# Mayfly_v0p5_outline.net
KiCad netlist of a schematic drawn in EAGLE
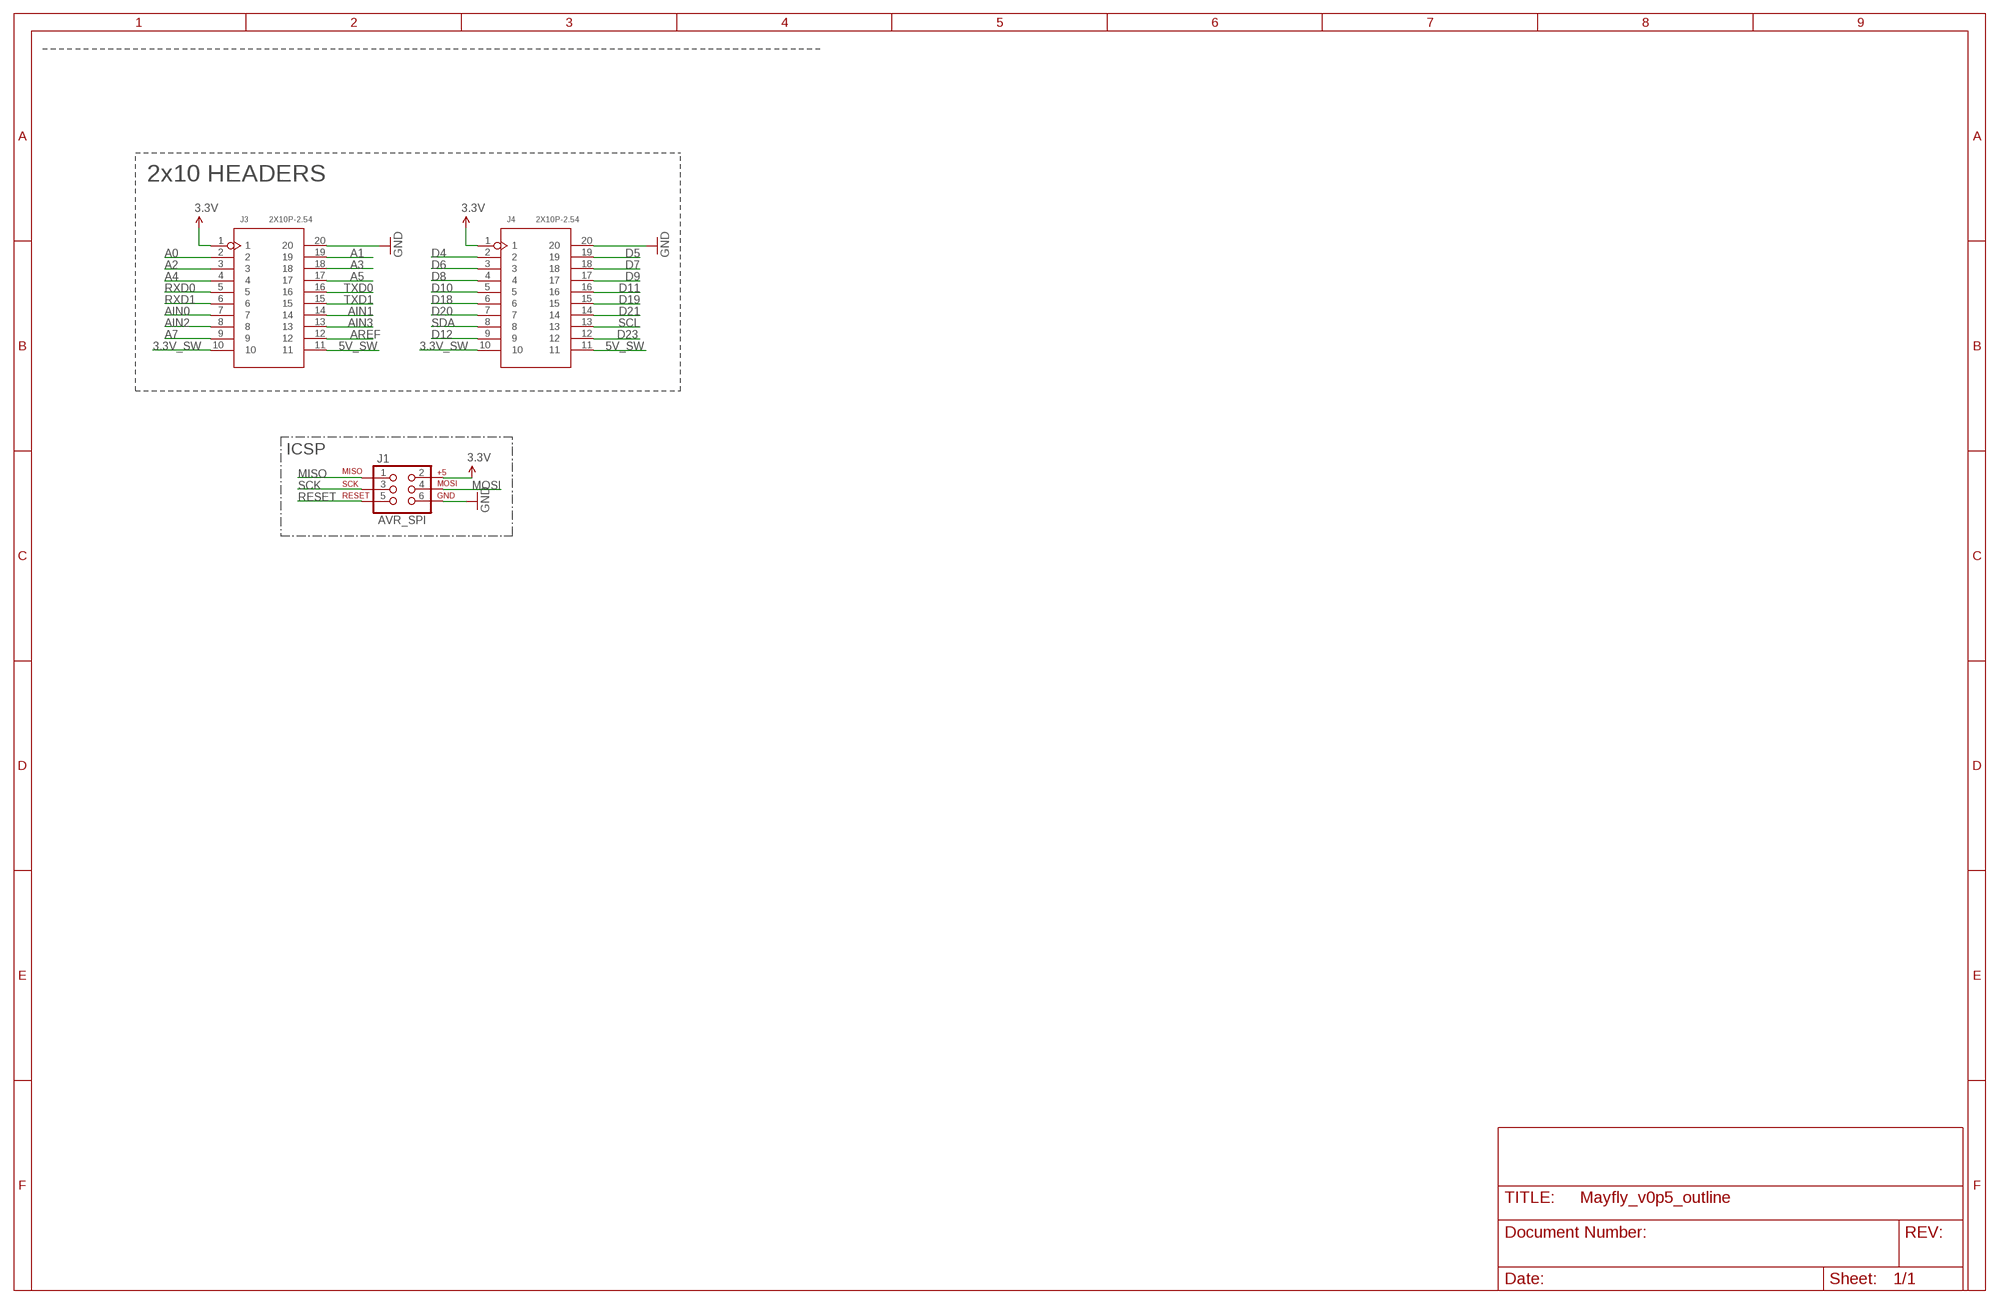
[diagram p0: schematic, sheet 1]

(export (version "E")
  (design (tool "Eeschema 10.0.6"))
  (components
    (comp (ref "J1")
      (value "AVR_SPI")
      (footprint "eagle-import:2X3-NS")
      (libsource (lib "eagle-import") (part "AVR_SPI_PRG_6NS"))
    )
    (comp (ref "J3")
      (value "2X10P-2.54")
      (footprint "eagle-import:H2X10-2.54")
      (fields (field (name "MPN") "F185-1210A0BA1"))
      (libsource (lib "eagle-import") (part "DIP-BLACK-FEMALE-HEADER(2X10P-2.54)-2.54"))
    )
    (comp (ref "J4")
      (value "2X10P-2.54")
      (footprint "eagle-import:H2X10-2.54")
      (fields (field (name "MPN") "F185-1210A0BA1"))
      (libsource (lib "eagle-import") (part "DIP-BLACK-FEMALE-HEADER(2X10P-2.54)-2.54"))
    )
  )
  (nets
    (net (code "1") (name "/3.3V_SW") (class "Default")
      (node (ref "J3") (pin "10") (pinfunction "10_10") (pintype "bidirectional"))
      (node (ref "J4") (pin "10") (pinfunction "10_10") (pintype "bidirectional"))
    )
    (net (code "2") (name "/5V_SW") (class "Default")
      (node (ref "J3") (pin "11") (pinfunction "11_11") (pintype "bidirectional"))
      (node (ref "J4") (pin "11") (pinfunction "11_11") (pintype "bidirectional"))
    )
    (net (code "3") (name "/A0") (class "Default")
      (node (ref "J3") (pin "2") (pinfunction "2_2") (pintype "bidirectional"))
    )
    (net (code "4") (name "/A1") (class "Default")
      (node (ref "J3") (pin "19") (pinfunction "19_19") (pintype "bidirectional"))
    )
    (net (code "5") (name "/A2") (class "Default")
      (node (ref "J3") (pin "3") (pinfunction "3_3") (pintype "bidirectional"))
    )
    (net (code "6") (name "/A3") (class "Default")
      (node (ref "J3") (pin "18") (pinfunction "18_18") (pintype "bidirectional"))
    )
    (net (code "7") (name "/A4") (class "Default")
      (node (ref "J3") (pin "4") (pinfunction "4_4") (pintype "bidirectional"))
    )
    (net (code "8") (name "/A5") (class "Default")
      (node (ref "J3") (pin "17") (pinfunction "17_17") (pintype "bidirectional"))
    )
    (net (code "9") (name "/A7") (class "Default")
      (node (ref "J3") (pin "9") (pinfunction "9_9") (pintype "bidirectional"))
    )
    (net (code "10") (name "/AIN0") (class "Default")
      (node (ref "J3") (pin "7") (pinfunction "7_7") (pintype "bidirectional"))
    )
    (net (code "11") (name "/AIN1") (class "Default")
      (node (ref "J3") (pin "14") (pinfunction "14_14") (pintype "bidirectional"))
    )
    (net (code "12") (name "/AIN2") (class "Default")
      (node (ref "J3") (pin "8") (pinfunction "8_8") (pintype "bidirectional"))
    )
    (net (code "13") (name "/AIN3") (class "Default")
      (node (ref "J3") (pin "13") (pinfunction "13_13") (pintype "bidirectional"))
    )
    (net (code "14") (name "/AREF") (class "Default")
      (node (ref "J3") (pin "12") (pinfunction "12_12") (pintype "bidirectional"))
    )
    (net (code "15") (name "/D4") (class "Default")
      (node (ref "J4") (pin "2") (pinfunction "2_2") (pintype "bidirectional"))
    )
    (net (code "16") (name "/D5") (class "Default")
      (node (ref "J4") (pin "19") (pinfunction "19_19") (pintype "bidirectional"))
    )
    (net (code "17") (name "/D6") (class "Default")
      (node (ref "J4") (pin "3") (pinfunction "3_3") (pintype "bidirectional"))
    )
    (net (code "18") (name "/D7") (class "Default")
      (node (ref "J4") (pin "18") (pinfunction "18_18") (pintype "bidirectional"))
    )
    (net (code "19") (name "/D8") (class "Default")
      (node (ref "J4") (pin "4") (pinfunction "4_4") (pintype "bidirectional"))
    )
    (net (code "20") (name "/D9") (class "Default")
      (node (ref "J4") (pin "17") (pinfunction "17_17") (pintype "bidirectional"))
    )
    (net (code "21") (name "/D10") (class "Default")
      (node (ref "J4") (pin "5") (pinfunction "5_5") (pintype "bidirectional"))
    )
    (net (code "22") (name "/D11") (class "Default")
      (node (ref "J4") (pin "16") (pinfunction "16_16") (pintype "bidirectional"))
    )
    (net (code "23") (name "/D12") (class "Default")
      (node (ref "J4") (pin "9") (pinfunction "9_9") (pintype "bidirectional"))
    )
    (net (code "24") (name "/D18") (class "Default")
      (node (ref "J4") (pin "6") (pinfunction "6_6") (pintype "bidirectional"))
    )
    (net (code "25") (name "/D19") (class "Default")
      (node (ref "J4") (pin "15") (pinfunction "15_15") (pintype "bidirectional"))
    )
    (net (code "26") (name "/D20") (class "Default")
      (node (ref "J4") (pin "7") (pinfunction "7_7") (pintype "bidirectional"))
    )
    (net (code "27") (name "/D21") (class "Default")
      (node (ref "J4") (pin "14") (pinfunction "14_14") (pintype "bidirectional"))
    )
    (net (code "28") (name "/D23") (class "Default")
      (node (ref "J4") (pin "12") (pinfunction "12_12") (pintype "bidirectional"))
    )
    (net (code "29") (name "/MISO") (class "Default")
      (node (ref "J1") (pin "1") (pinfunction "1_1") (pintype "passive"))
    )
    (net (code "30") (name "/MOSI") (class "Default")
      (node (ref "J1") (pin "4") (pinfunction "4_4") (pintype "passive"))
    )
    (net (code "31") (name "/RESET") (class "Default")
      (node (ref "J1") (pin "5") (pinfunction "5_5") (pintype "passive"))
    )
    (net (code "32") (name "/RXD0") (class "Default")
      (node (ref "J3") (pin "5") (pinfunction "5_5") (pintype "bidirectional"))
    )
    (net (code "33") (name "/RXD1") (class "Default")
      (node (ref "J3") (pin "6") (pinfunction "6_6") (pintype "bidirectional"))
    )
    (net (code "34") (name "/SCK") (class "Default")
      (node (ref "J1") (pin "3") (pinfunction "3_3") (pintype "passive"))
    )
    (net (code "35") (name "/SCL") (class "Default")
      (node (ref "J4") (pin "13") (pinfunction "13_13") (pintype "bidirectional"))
    )
    (net (code "36") (name "/SDA") (class "Default")
      (node (ref "J4") (pin "8") (pinfunction "8_8") (pintype "bidirectional"))
    )
    (net (code "37") (name "/TXD0") (class "Default")
      (node (ref "J3") (pin "16") (pinfunction "16_16") (pintype "bidirectional"))
    )
    (net (code "38") (name "/TXD1") (class "Default")
      (node (ref "J3") (pin "15") (pinfunction "15_15") (pintype "bidirectional"))
    )
    (net (code "39") (name "3.3V") (class "Default")
      (node (ref "J1") (pin "2") (pinfunction "2_2") (pintype "passive"))
      (node (ref "J3") (pin "1") (pinfunction "1_1") (pintype "bidirectional"))
      (node (ref "J4") (pin "1") (pinfunction "1_1") (pintype "bidirectional"))
    )
    (net (code "40") (name "GND") (class "Default")
      (node (ref "J1") (pin "6") (pinfunction "6_6") (pintype "passive"))
      (node (ref "J3") (pin "20") (pinfunction "20_20") (pintype "bidirectional"))
      (node (ref "J4") (pin "20") (pinfunction "20_20") (pintype "bidirectional"))
    )
  )
)
